# 1ssrCompactBoard.net
KiCad netlist of a schematic drawn in EAGLE
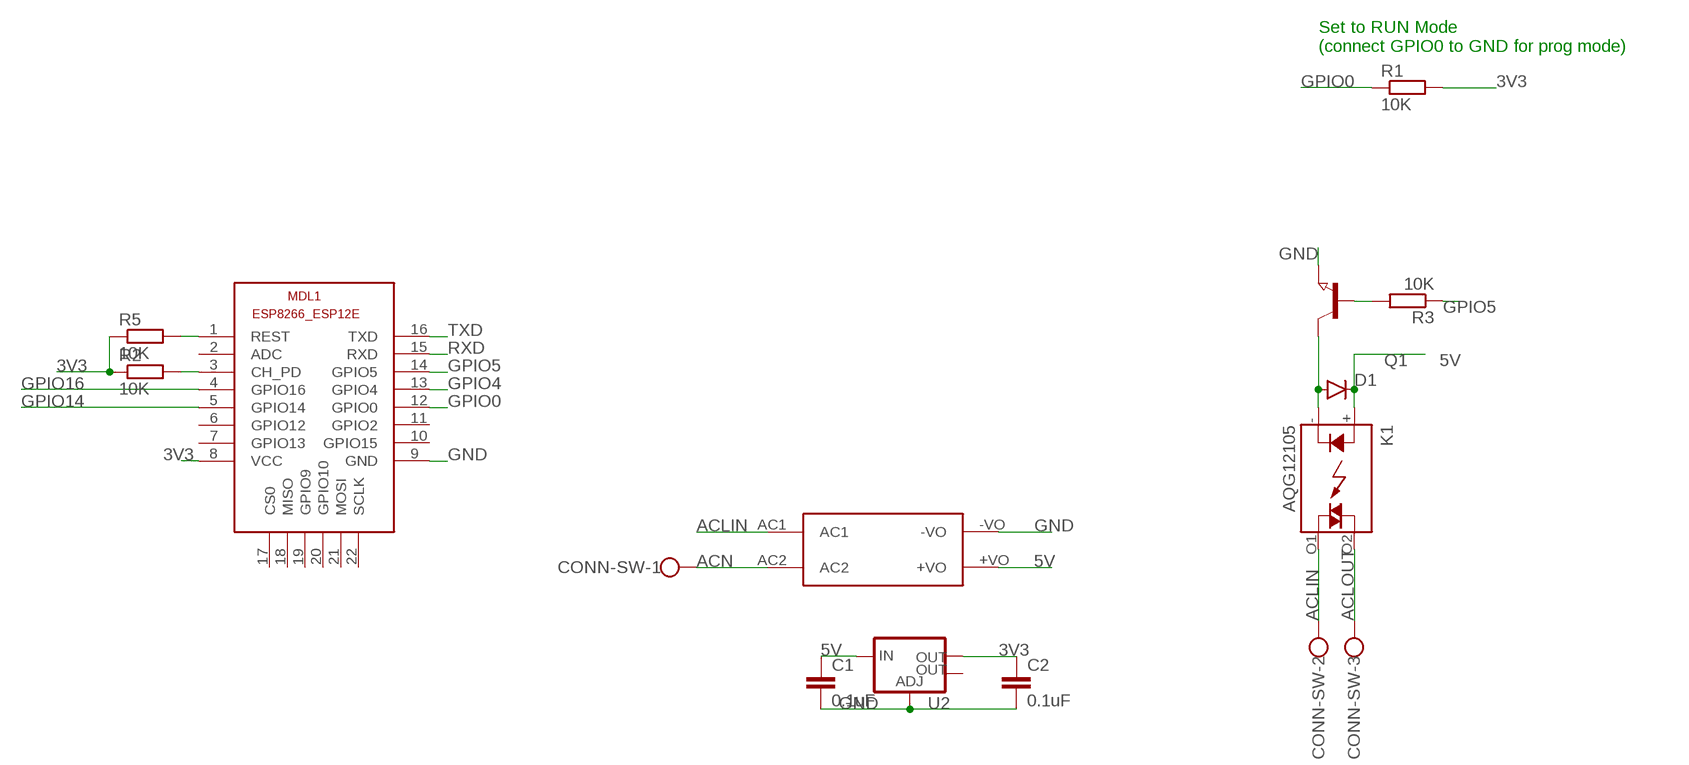
[diagram p0: schematic, sheet 1]

(export (version "E")
  (design (tool "Eeschema 10.0.6"))
  (components
    (comp (ref "C1")
      (value "0.1uF")
      (footprint "eagle-import:0603-CAP")
      (libsource (lib "eagle-import") (part "0.1UF-25V-5%(0603)"))
    )
    (comp (ref "C2")
      (value "0.1uF")
      (footprint "eagle-import:0603-CAP")
      (libsource (lib "eagle-import") (part "0.1UF-25V-5%(0603)"))
    )
    (comp (ref "CONN-SW")
      (value "W237-103")
      (footprint "eagle-import:W237-103")
      (fields (field (name "MPN") "237-103"))
      (libsource (lib "eagle-import") (part "W237-103"))
    )
    (comp (ref "D1")
      (value "DIODESMA")
      (footprint "eagle-import:SMA-DIODE")
      (libsource (lib "eagle-import") (part "DIODESMA"))
    )
    (comp (ref "K1")
      (value "AQG12105")
      (footprint "eagle-import:AQG")
      (fields (field (name "MF") "AROMAT/ MATSUSHITA"))
      (libsource (lib "eagle-import") (part "AQG12105"))
    )
    (comp (ref "MDL1")
      (value "ESP8266-12EESP8266-ESP12E")
      (footprint "eagle-import:ESP8266-ESP12E")
      (libsource (lib "eagle-import") (part "ESP8266-12EESP8266-ESP12E"))
    )
    (comp (ref "Q1")
      (value "NPN-TRANSISTOR_SOT23")
      (footprint "eagle-import:SOT23")
      (libsource (lib "eagle-import") (part "NPN-TRANSISTOR_SOT23"))
    )
    (comp (ref "R1")
      (value "10K")
      (footprint "eagle-import:R0805")
      (libsource (lib "eagle-import") (part "R-EU_R0805"))
    )
    (comp (ref "R2")
      (value "10K")
      (footprint "eagle-import:R0805")
      (libsource (lib "eagle-import") (part "R-EU_R0805"))
    )
    (comp (ref "R3")
      (value "10K")
      (footprint "eagle-import:R0805")
      (libsource (lib "eagle-import") (part "R-EU_R0805"))
    )
    (comp (ref "R5")
      (value "10K")
      (footprint "eagle-import:R0805")
      (libsource (lib "eagle-import") (part "R-EU_R0805"))
    )
    (comp (ref "U$4")
      (value "HLK-PM01")
      (footprint "eagle-import:HLK-PM01")
      (libsource (lib "eagle-import") (part "HLK-PM01"))
    )
    (comp (ref "U2")
      (value "V_REG_LM1117SOT223")
      (footprint "eagle-import:SOT223")
      (libsource (lib "eagle-import") (part "V_REG_LM1117SOT223"))
    )
  )
  (nets
    (net (code "1") (name "/3V3") (class "Default")
      (node (ref "C2") (pin "1") (pinfunction "1_1") (pintype "passive"))
      (node (ref "MDL1") (pin "8") (pinfunction "VCC_8") (pintype "bidirectional"))
      (node (ref "R1") (pin "2") (pinfunction "2_2") (pintype "passive"))
      (node (ref "R2") (pin "1") (pinfunction "1_1") (pintype "passive"))
      (node (ref "R5") (pin "1") (pinfunction "1_1") (pintype "passive"))
      (node (ref "U2") (pin "2") (pinfunction "OUT_2") (pintype "output"))
    )
    (net (code "2") (name "/5V") (class "Default")
      (node (ref "C1") (pin "1") (pinfunction "1_1") (pintype "passive"))
      (node (ref "D1") (pin "C") (pinfunction "C_C") (pintype "passive"))
      (node (ref "K1") (pin "+") (pinfunction "A_+") (pintype "passive"))
      (node (ref "U$4") (pin "+VO") (pinfunction "+VO_+VO") (pintype "bidirectional"))
      (node (ref "U2") (pin "3") (pinfunction "IN_3") (pintype "input"))
    )
    (net (code "3") (name "/ACLIN") (class "Default")
      (node (ref "CONN-SW") (pin "2") (pinfunction "KL_2") (pintype "passive"))
      (node (ref "K1") (pin "O1") (pinfunction "DS2_O1") (pintype "passive"))
      (node (ref "U$4") (pin "AC1") (pinfunction "AC1_AC1") (pintype "bidirectional"))
    )
    (net (code "4") (name "/ACLOUT") (class "Default")
      (node (ref "CONN-SW") (pin "3") (pinfunction "KL_3") (pintype "passive"))
      (node (ref "K1") (pin "O2") (pinfunction "DS1_O2") (pintype "passive"))
    )
    (net (code "5") (name "/ACN") (class "Default")
      (node (ref "CONN-SW") (pin "1") (pinfunction "KL_1") (pintype "passive"))
      (node (ref "U$4") (pin "AC2") (pinfunction "AC2_AC2") (pintype "bidirectional"))
    )
    (net (code "6") (name "/GND") (class "Default")
      (node (ref "C1") (pin "2") (pinfunction "2_2") (pintype "passive"))
      (node (ref "C2") (pin "2") (pinfunction "2_2") (pintype "passive"))
      (node (ref "MDL1") (pin "9") (pinfunction "GND_9") (pintype "bidirectional"))
      (node (ref "Q1") (pin "2") (pinfunction "E_2") (pintype "passive"))
      (node (ref "U$4") (pin "-VO") (pinfunction "-VO_-VO") (pintype "bidirectional"))
      (node (ref "U2") (pin "1") (pinfunction "ADJ_1") (pintype "input"))
    )
    (net (code "7") (name "/GPIO0") (class "Default")
      (node (ref "MDL1") (pin "12") (pinfunction "GPIO0_12") (pintype "bidirectional"))
      (node (ref "R1") (pin "1") (pinfunction "1_1") (pintype "passive"))
    )
    (net (code "8") (name "/GPIO4") (class "Default")
      (node (ref "MDL1") (pin "13") (pinfunction "GPIO4_13") (pintype "bidirectional"))
    )
    (net (code "9") (name "/GPIO5") (class "Default")
      (node (ref "MDL1") (pin "14") (pinfunction "GPIO5_14") (pintype "bidirectional"))
      (node (ref "R3") (pin "1") (pinfunction "1_1") (pintype "passive"))
    )
    (net (code "10") (name "/GPIO14") (class "Default")
      (node (ref "MDL1") (pin "5") (pinfunction "GPIO14_5") (pintype "bidirectional"))
    )
    (net (code "11") (name "/GPIO16") (class "Default")
      (node (ref "MDL1") (pin "4") (pinfunction "GPIO16_4") (pintype "bidirectional"))
    )
    (net (code "12") (name "/RXD") (class "Default")
      (node (ref "MDL1") (pin "15") (pinfunction "RXD_15") (pintype "bidirectional"))
    )
    (net (code "13") (name "/TXD") (class "Default")
      (node (ref "MDL1") (pin "16") (pinfunction "TXD_16") (pintype "bidirectional"))
    )
    (net (code "14") (name "Net-(K1-K)") (class "Default")
      (node (ref "D1") (pin "A") (pinfunction "A_A") (pintype "passive"))
      (node (ref "K1") (pin "-") (pinfunction "K_-") (pintype "passive"))
      (node (ref "Q1") (pin "3") (pinfunction "C_3") (pintype "passive"))
    )
    (net (code "15") (name "Net-(MDL1-CH_PD)") (class "Default")
      (node (ref "MDL1") (pin "3") (pinfunction "CH_PD_3") (pintype "bidirectional"))
      (node (ref "R2") (pin "2") (pinfunction "2_2") (pintype "passive"))
    )
    (net (code "16") (name "Net-(MDL1-REST)") (class "Default")
      (node (ref "MDL1") (pin "1") (pinfunction "REST_1") (pintype "bidirectional"))
      (node (ref "R5") (pin "2") (pinfunction "2_2") (pintype "passive"))
    )
    (net (code "17") (name "Net-(Q1-B)") (class "Default")
      (node (ref "Q1") (pin "1") (pinfunction "B_1") (pintype "passive"))
      (node (ref "R3") (pin "2") (pinfunction "2_2") (pintype "passive"))
    )
    (net (code "18") (name "unconnected-(MDL1-ADC-Pad2)") (class "Default")
      (node (ref "MDL1") (pin "2") (pinfunction "ADC_2") (pintype "bidirectional"))
    )
    (net (code "19") (name "unconnected-(MDL1-CS0-Pad17)") (class "Default")
      (node (ref "MDL1") (pin "17") (pinfunction "CS0_17") (pintype "bidirectional"))
    )
    (net (code "20") (name "unconnected-(MDL1-GPIO2-Pad11)") (class "Default")
      (node (ref "MDL1") (pin "11") (pinfunction "GPIO2_11") (pintype "bidirectional"))
    )
    (net (code "21") (name "unconnected-(MDL1-GPIO9-Pad19)") (class "Default")
      (node (ref "MDL1") (pin "19") (pinfunction "GPIO9_19") (pintype "bidirectional"))
    )
    (net (code "22") (name "unconnected-(MDL1-GPIO10-Pad20)") (class "Default")
      (node (ref "MDL1") (pin "20") (pinfunction "GPIO10_20") (pintype "bidirectional"))
    )
    (net (code "23") (name "unconnected-(MDL1-GPIO12-Pad6)") (class "Default")
      (node (ref "MDL1") (pin "6") (pinfunction "GPIO12_6") (pintype "bidirectional"))
    )
    (net (code "24") (name "unconnected-(MDL1-GPIO13-Pad7)") (class "Default")
      (node (ref "MDL1") (pin "7") (pinfunction "GPIO13_7") (pintype "bidirectional"))
    )
    (net (code "25") (name "unconnected-(MDL1-GPIO15-Pad10)") (class "Default")
      (node (ref "MDL1") (pin "10") (pinfunction "GPIO15_10") (pintype "bidirectional"))
    )
    (net (code "26") (name "unconnected-(MDL1-MISO-Pad18)") (class "Default")
      (node (ref "MDL1") (pin "18") (pinfunction "MISO_18") (pintype "bidirectional"))
    )
    (net (code "27") (name "unconnected-(MDL1-MOSI-Pad21)") (class "Default")
      (node (ref "MDL1") (pin "21") (pinfunction "MOSI_21") (pintype "bidirectional"))
    )
    (net (code "28") (name "unconnected-(MDL1-SCLK-Pad22)") (class "Default")
      (node (ref "MDL1") (pin "22") (pinfunction "SCLK_22") (pintype "bidirectional"))
    )
    (net (code "29") (name "unconnected-(U2-OUT-Pad4)") (class "Default")
      (node (ref "U2") (pin "4") (pinfunction "OUT_4") (pintype "output"))
    )
  )
)
